# DispenM2.net
KiCad netlist of a schematic drawn in EAGLE
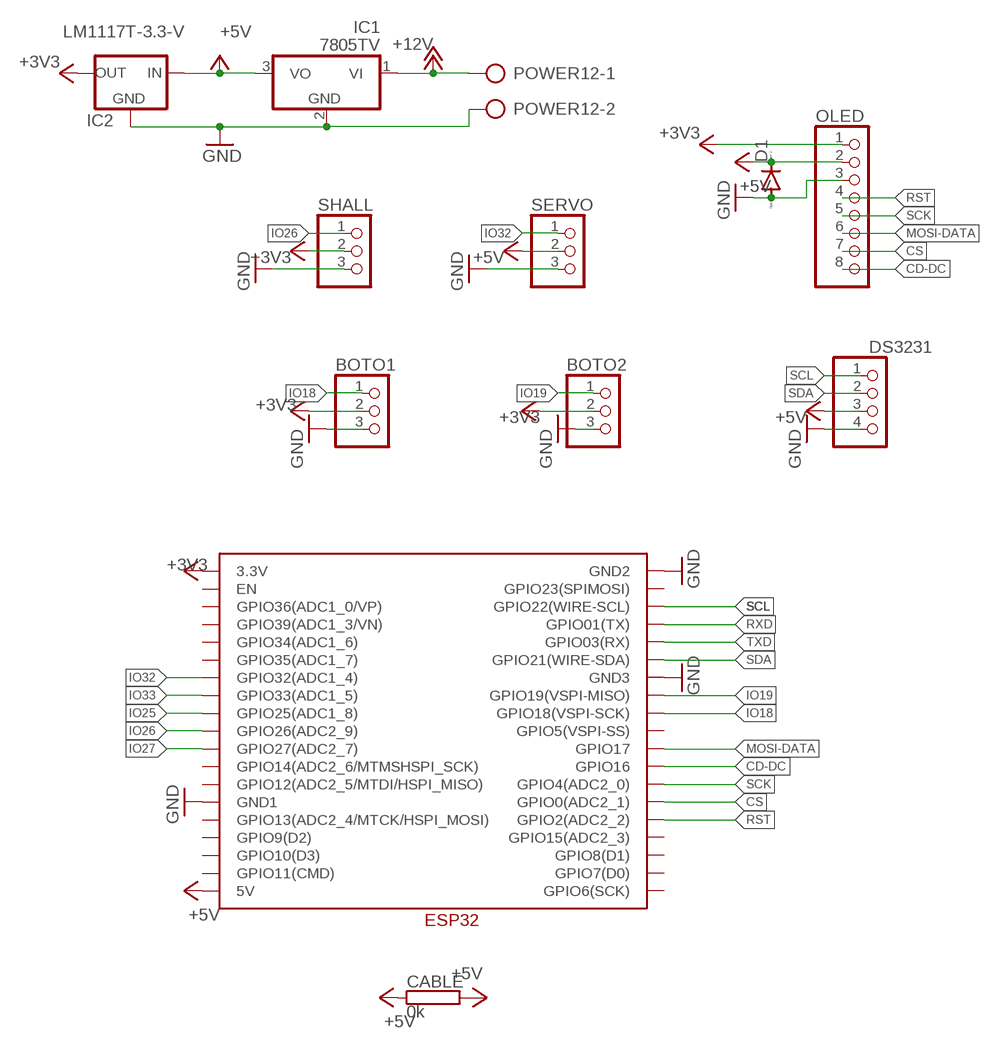
[diagram p0: schematic, sheet 1]

(export (version "E")
  (design (tool "Eeschema 10.0.6"))
  (components
    (comp (ref "BOTO1")
      (value "PINHD-1X3")
      (footprint "eagle-import:1X03")
      (libsource (lib "eagle-import") (part "PINHD-1X3"))
    )
    (comp (ref "BOTO2")
      (value "PINHD-1X3")
      (footprint "eagle-import:1X03")
      (libsource (lib "eagle-import") (part "PINHD-1X3"))
    )
    (comp (ref "CABLE")
      (value "0k")
      (footprint "eagle-import:CA4100")
      (libsource (lib "eagle-import") (part "RCA4100"))
    )
    (comp (ref "D1")
      (value "DIODE-SOD81")
      (footprint "eagle-import:SOD81")
      (libsource (lib "eagle-import") (part "DIODE-SOD81"))
    )
    (comp (ref "DS3231")
      (value "PINHD-1X4")
      (footprint "eagle-import:1X04")
      (libsource (lib "eagle-import") (part "PINHD-1X4"))
    )
    (comp (ref "IC1")
      (value "7805TV")
      (footprint "eagle-import:TO220V")
      (libsource (lib "eagle-import") (part "78TV05"))
    )
    (comp (ref "IC2")
      (value "LM1117T-3.3-V")
      (footprint "eagle-import:TO220V")
      (libsource (lib "eagle-import") (part "LM1117T--V3.3"))
    )
    (comp (ref "OLED")
      (value "PINHD-1X8")
      (footprint "eagle-import:1X08")
      (libsource (lib "eagle-import") (part "PINHD-1X8"))
    )
    (comp (ref "POWER12")
      (value "AK500/2")
      (footprint "eagle-import:AK500_2")
      (libsource (lib "eagle-import") (part "AK500/2"))
    )
    (comp (ref "SERVO")
      (value "PINHD-1X3")
      (footprint "eagle-import:1X03")
      (libsource (lib "eagle-import") (part "PINHD-1X3"))
    )
    (comp (ref "SHALL")
      (value "PINHD-1X3")
      (footprint "eagle-import:1X03")
      (libsource (lib "eagle-import") (part "PINHD-1X3"))
    )
    (comp (ref "U$1")
      (value "ESP32WESP32W")
      (footprint "eagle-import:ESP32W")
      (libsource (lib "eagle-import") (part "ESP32WESP32W"))
    )
  )
  (nets
    (net (code "1") (name "+3V3") (class "Default")
      (node (ref "BOTO1") (pin "2") (pinfunction "2_2") (pintype "passive"))
      (node (ref "BOTO2") (pin "2") (pinfunction "2_2") (pintype "passive"))
      (node (ref "IC2") (pin "2") (pinfunction "OUT_2") (pintype "passive"))
      (node (ref "OLED") (pin "1") (pinfunction "1_1") (pintype "passive"))
      (node (ref "SHALL") (pin "2") (pinfunction "2_2") (pintype "passive"))
      (node (ref "U$1") (pin "3.3V") (pinfunction "3.3V_3.3V") (pintype "bidirectional"))
    )
    (net (code "2") (name "+5V") (class "Default")
      (node (ref "CABLE") (pin "1") (pinfunction "1_1") (pintype "passive"))
      (node (ref "CABLE") (pin "2") (pinfunction "2_2") (pintype "passive"))
      (node (ref "D1") (pin "C") (pinfunction "C_C") (pintype "passive"))
      (node (ref "DS3231") (pin "3") (pinfunction "3_3") (pintype "passive"))
      (node (ref "IC1") (pin "3") (pinfunction "VO_3") (pintype "passive"))
      (node (ref "IC2") (pin "3") (pinfunction "IN_3") (pintype "input"))
      (node (ref "OLED") (pin "2") (pinfunction "2_2") (pintype "passive"))
      (node (ref "SERVO") (pin "2") (pinfunction "2_2") (pintype "passive"))
      (node (ref "U$1") (pin "5V") (pinfunction "5V_5V") (pintype "bidirectional"))
    )
    (net (code "3") (name "+12V") (class "Default")
      (node (ref "IC1") (pin "1") (pinfunction "VI_1") (pintype "input"))
      (node (ref "POWER12") (pin "1") (pinfunction "KL_1") (pintype "passive"))
    )
    (net (code "4") (name "CD-DC") (class "Default")
      (node (ref "OLED") (pin "8") (pinfunction "8_8") (pintype "passive"))
      (node (ref "U$1") (pin "GPIO16") (pinfunction "GPIO16_GPIO16") (pintype "bidirectional"))
    )
    (net (code "5") (name "CS") (class "Default")
      (node (ref "OLED") (pin "7") (pinfunction "7_7") (pintype "passive"))
      (node (ref "U$1") (pin "GPIO0") (pinfunction "GPIO0(ADC2_1)_GPIO0") (pintype "bidirectional"))
    )
    (net (code "6") (name "GND") (class "Default")
      (node (ref "BOTO1") (pin "3") (pinfunction "3_3") (pintype "passive"))
      (node (ref "BOTO2") (pin "3") (pinfunction "3_3") (pintype "passive"))
      (node (ref "D1") (pin "A") (pinfunction "A_A") (pintype "passive"))
      (node (ref "DS3231") (pin "4") (pinfunction "4_4") (pintype "passive"))
      (node (ref "IC1") (pin "2") (pinfunction "GND_2") (pintype "passive"))
      (node (ref "IC2") (pin "1") (pinfunction "GND_1") (pintype "input"))
      (node (ref "OLED") (pin "3") (pinfunction "3_3") (pintype "passive"))
      (node (ref "POWER12") (pin "2") (pinfunction "KL_2") (pintype "passive"))
      (node (ref "SERVO") (pin "3") (pinfunction "3_3") (pintype "passive"))
      (node (ref "SHALL") (pin "3") (pinfunction "3_3") (pintype "passive"))
      (node (ref "U$1") (pin "GND1") (pinfunction "GND1_GND1") (pintype "bidirectional"))
      (node (ref "U$1") (pin "GND2") (pinfunction "GND2_GND2") (pintype "bidirectional"))
      (node (ref "U$1") (pin "GND3") (pinfunction "GND3_GND3") (pintype "bidirectional"))
    )
    (net (code "7") (name "IO18") (class "Default")
      (node (ref "BOTO1") (pin "1") (pinfunction "1_1") (pintype "passive"))
      (node (ref "U$1") (pin "GPIO18") (pinfunction "GPIO18(VSPI-SCK)_GPIO18") (pintype "bidirectional"))
    )
    (net (code "8") (name "IO19") (class "Default")
      (node (ref "BOTO2") (pin "1") (pinfunction "1_1") (pintype "passive"))
      (node (ref "U$1") (pin "GPIO19") (pinfunction "GPIO19(VSPI-MISO)_GPIO19") (pintype "bidirectional"))
    )
    (net (code "9") (name "IO25") (class "Default")
      (node (ref "U$1") (pin "GPIO25") (pinfunction "GPIO25(ADC1_8)_GPIO25") (pintype "bidirectional"))
    )
    (net (code "10") (name "IO26") (class "Default")
      (node (ref "SHALL") (pin "1") (pinfunction "1_1") (pintype "passive"))
      (node (ref "U$1") (pin "GPIO26") (pinfunction "GPIO26(ADC2_9)_GPIO26") (pintype "bidirectional"))
    )
    (net (code "11") (name "IO27") (class "Default")
      (node (ref "U$1") (pin "GPIO27") (pinfunction "GPIO27(ADC2_7)_GPIO27") (pintype "bidirectional"))
    )
    (net (code "12") (name "IO32") (class "Default")
      (node (ref "SERVO") (pin "1") (pinfunction "1_1") (pintype "passive"))
      (node (ref "U$1") (pin "GPIO32") (pinfunction "GPIO32(ADC1_4)_GPIO32") (pintype "bidirectional"))
    )
    (net (code "13") (name "IO33") (class "Default")
      (node (ref "U$1") (pin "GPIO33") (pinfunction "GPIO33(ADC1_5)_GPIO33") (pintype "bidirectional"))
    )
    (net (code "14") (name "MOSI-DATA") (class "Default")
      (node (ref "OLED") (pin "6") (pinfunction "6_6") (pintype "passive"))
      (node (ref "U$1") (pin "GPIO17") (pinfunction "GPIO17_GPIO17") (pintype "bidirectional"))
    )
    (net (code "15") (name "RST") (class "Default")
      (node (ref "OLED") (pin "4") (pinfunction "4_4") (pintype "passive"))
      (node (ref "U$1") (pin "GPIO2") (pinfunction "GPIO2(ADC2_2)_GPIO2") (pintype "bidirectional"))
    )
    (net (code "16") (name "RXD") (class "Default")
      (node (ref "U$1") (pin "TX") (pinfunction "GPIO01(TX)_TX") (pintype "bidirectional"))
    )
    (net (code "17") (name "SCK") (class "Default")
      (node (ref "OLED") (pin "5") (pinfunction "5_5") (pintype "passive"))
      (node (ref "U$1") (pin "GPIO4") (pinfunction "GPIO4(ADC2_0)_GPIO4") (pintype "bidirectional"))
    )
    (net (code "18") (name "SCL") (class "Default")
      (node (ref "DS3231") (pin "1") (pinfunction "1_1") (pintype "passive"))
      (node (ref "U$1") (pin "GPIO22") (pinfunction "GPIO22(WIRE-SCL)_GPIO22") (pintype "bidirectional"))
    )
    (net (code "19") (name "SDA") (class "Default")
      (node (ref "DS3231") (pin "2") (pinfunction "2_2") (pintype "passive"))
      (node (ref "U$1") (pin "GPIO21") (pinfunction "GPIO21(WIRE-SDA)_GPIO21") (pintype "bidirectional"))
    )
    (net (code "20") (name "TXD") (class "Default")
      (node (ref "U$1") (pin "RX") (pinfunction "GPIO03(RX)_RX") (pintype "bidirectional"))
    )
    (net (code "21") (name "unconnected-(U$1-GPIO5(VSPI-SS)-PadGPIO5)") (class "Default")
      (node (ref "U$1") (pin "GPIO5") (pinfunction "GPIO5(VSPI-SS)_GPIO5") (pintype "bidirectional"))
    )
    (net (code "22") (name "unconnected-(U$1-GPIO6(SCK)-PadCLK)") (class "Default")
      (node (ref "U$1") (pin "CLK") (pinfunction "GPIO6(SCK)_CLK") (pintype "bidirectional"))
    )
    (net (code "23") (name "unconnected-(U$1-GPIO7(D0)-PadSDO)") (class "Default")
      (node (ref "U$1") (pin "SDO") (pinfunction "GPIO7(D0)_SDO") (pintype "bidirectional"))
    )
    (net (code "24") (name "unconnected-(U$1-GPIO8(D1)-PadSDI)") (class "Default")
      (node (ref "U$1") (pin "SDI") (pinfunction "GPIO8(D1)_SDI") (pintype "bidirectional"))
    )
    (net (code "25") (name "unconnected-(U$1-GPIO9(D2)-PadD2)") (class "Default")
      (node (ref "U$1") (pin "D2") (pinfunction "GPIO9(D2)_D2") (pintype "bidirectional"))
    )
    (net (code "26") (name "unconnected-(U$1-GPIO10(D3)-PadD3)") (class "Default")
      (node (ref "U$1") (pin "D3") (pinfunction "GPIO10(D3)_D3") (pintype "bidirectional"))
    )
    (net (code "27") (name "unconnected-(U$1-GPIO11(CMD)-PadCMD)") (class "Default")
      (node (ref "U$1") (pin "CMD") (pinfunction "GPIO11(CMD)_CMD") (pintype "bidirectional"))
    )
    (net (code "28") (name "unconnected-(U$1-GPIO12(ADC2_5{slash}MTDI{slash}HSPI_MISO)-PadGPIO12)") (class "Default")
      (node (ref "U$1") (pin "GPIO12") (pinfunction "GPIO12(ADC2_5/MTDI/HSPI_MISO)_GPIO12") (pintype "bidirectional"))
    )
    (net (code "29") (name "unconnected-(U$1-GPIO13(ADC2_4{slash}MTCK{slash}HSPI_MOSI)-PadGPIO13)") (class "Default")
      (node (ref "U$1") (pin "GPIO13") (pinfunction "GPIO13(ADC2_4/MTCK/HSPI_MOSI)_GPIO13") (pintype "bidirectional"))
    )
    (net (code "30") (name "unconnected-(U$1-GPIO14(ADC2_6{slash}MTMSHSPI_SCK)-PadGPIO14)") (class "Default")
      (node (ref "U$1") (pin "GPIO14") (pinfunction "GPIO14(ADC2_6/MTMSHSPI_SCK)_GPIO14") (pintype "bidirectional"))
    )
    (net (code "31") (name "unconnected-(U$1-GPIO15(ADC2_3)-PadGPIO15)") (class "Default")
      (node (ref "U$1") (pin "GPIO15") (pinfunction "GPIO15(ADC2_3)_GPIO15") (pintype "bidirectional"))
    )
    (net (code "32") (name "unconnected-(U$1-GPIO23(SPIMOSI)-PadGPIO23)") (class "Default")
      (node (ref "U$1") (pin "GPIO23") (pinfunction "GPIO23(SPIMOSI)_GPIO23") (pintype "bidirectional"))
    )
    (net (code "33") (name "unconnected-(U$1-GPIO34(ADC1_6)-PadGPIO34)") (class "Default")
      (node (ref "U$1") (pin "GPIO34") (pinfunction "GPIO34(ADC1_6)_GPIO34") (pintype "bidirectional"))
    )
    (net (code "34") (name "unconnected-(U$1-GPIO35(ADC1_7)-PadGPIO35)") (class "Default")
      (node (ref "U$1") (pin "GPIO35") (pinfunction "GPIO35(ADC1_7)_GPIO35") (pintype "bidirectional"))
    )
    (net (code "35") (name "unconnected-(U$1-GPIO36(ADC1_0{slash}VP)-PadVP)") (class "Default")
      (node (ref "U$1") (pin "VP") (pinfunction "GPIO36(ADC1_0/VP)_VP") (pintype "bidirectional"))
    )
    (net (code "36") (name "unconnected-(U$1-GPIO39(ADC1_3{slash}VN)-PadVN)") (class "Default")
      (node (ref "U$1") (pin "VN") (pinfunction "GPIO39(ADC1_3/VN)_VN") (pintype "bidirectional"))
    )
    (net (code "37") (name "unconnected-(U$1-PadEN)") (class "Default")
      (node (ref "U$1") (pin "EN") (pinfunction "EN_EN") (pintype "bidirectional"))
    )
  )
)
